# motor_driver_current_sensor.net
KiCad netlist of a schematic drawn in Altium Designer
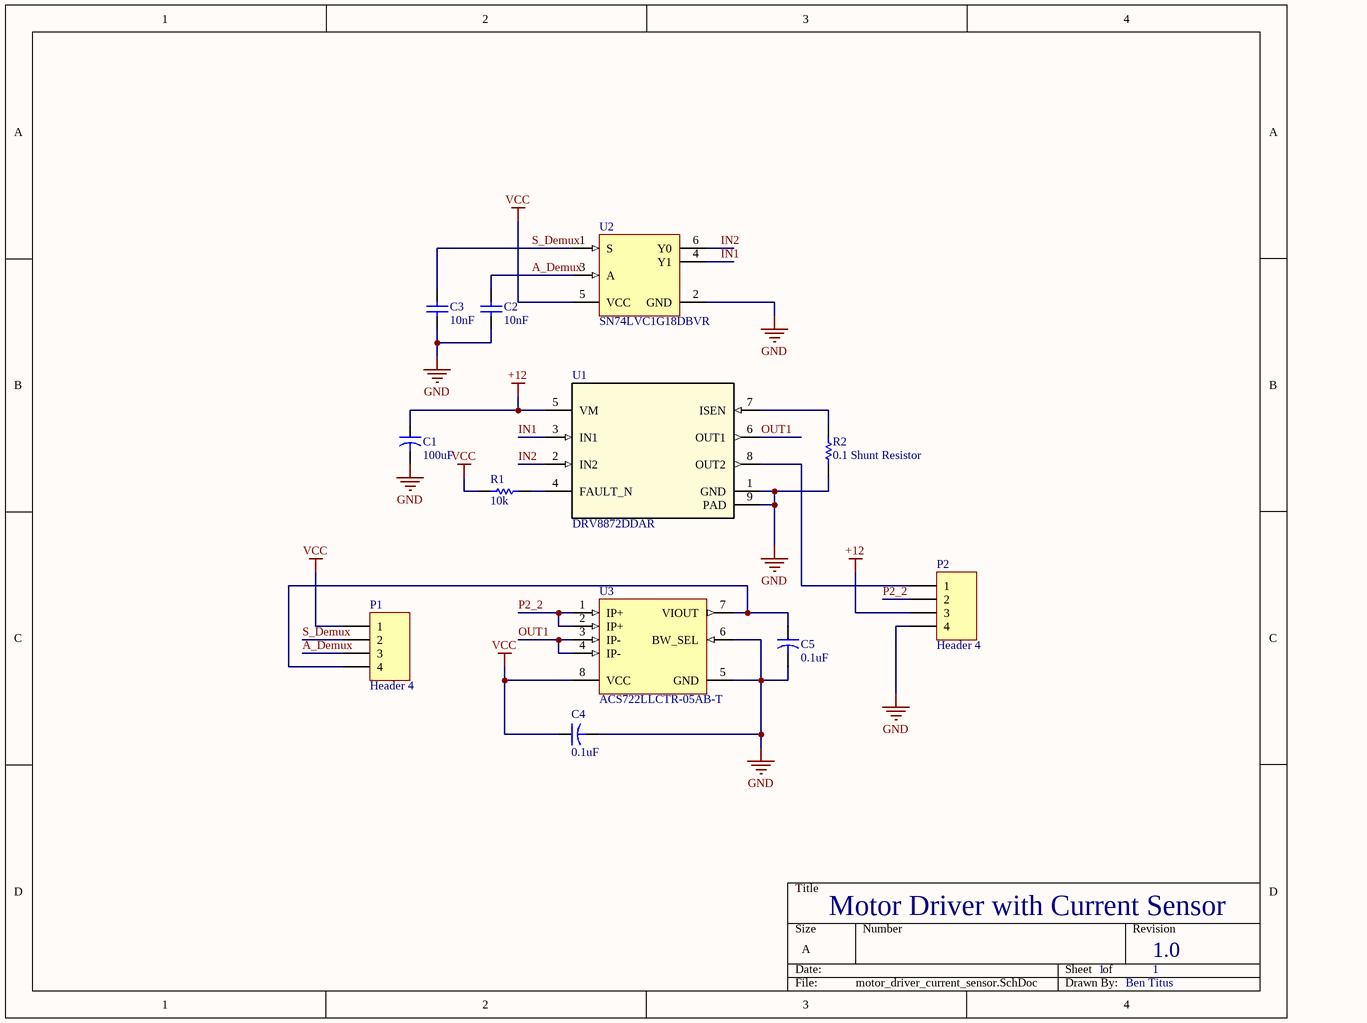
[diagram p0: motor_driver_current_sensor.SchDoc]

(export (version "E")
  (design (tool "Eeschema 10.0.6"))
  (components
    (comp (ref "C1")
      (value "100uF")
      (footprint "CAPR5-4X5")
      (description "100uF Filter Capacitor")
      (fields (field (name "PUBLISHER") "Altium Limited"))
      (libsource (lib "Miscellaneous Devices") (part "Cap2"))
    )
    (comp (ref "C2")
      (value "10nF")
      (footprint "CAPC0805(2012)145_L")
      (description "0805 (2012 Metric) Chip Capacitor")
      (libsource (lib "Altium Content Vault") (part "CAP_5"))
    )
    (comp (ref "C3")
      (value "10nF")
      (footprint "CAPC0805(2012)145_L")
      (description "0805 (2012 Metric) Chip Capacitor")
      (libsource (lib "Altium Content Vault") (part "CAP_5"))
    )
    (comp (ref "C4")
      (value "0.1uF")
      (footprint "CAPR5-4X5")
      (description "Capacitor")
      (fields (field (name "PUBLISHER") "Altium Limited"))
      (libsource (lib "Miscellaneous Devices") (part "Cap2"))
    )
    (comp (ref "C5")
      (value "0.1uF")
      (footprint "CAPR5-4X5")
      (description "Capacitor")
      (fields (field (name "PUBLISHER") "Altium Limited"))
      (libsource (lib "Miscellaneous Devices") (part "Cap2"))
    )
    (comp (ref "P1")
      (value "Header 4")
      (footprint "HDR1X4")
      (description "Header, 4-Pin")
      (fields (field (name "PUBLISHER") "Altium Limited"))
      (libsource (lib "Miscellaneous Connectors") (part "Header 4"))
    )
    (comp (ref "P2")
      (value "Header 4")
      (footprint "HDR1X4")
      (description "Header, 4-Pin")
      (fields (field (name "PUBLISHER") "Altium Limited"))
      (libsource (lib "Miscellaneous Connectors") (part "Header 4"))
    )
    (comp (ref "R1")
      (value "10k")
      (footprint "RESC0805(2012)_L")
      (description "0805 (2012 Metric) Chip Resistor")
      (libsource (lib "Altium Content Vault") (part "RES_3"))
    )
    (comp (ref "R2")
      (value "0.1 Shunt Resistor")
      (footprint "RESC2512(6432)_L")
      (description "2512 (6432 Metric) Chip Resistor")
      (libsource (lib "Altium Content Vault") (part "RES_3"))
    )
    (comp (ref "U1")
      (value "DRV8872DDAR")
      (footprint "DDA0008H_N")
      (description "Imported")
      (fields
        (field (name "ALTERNATE_PARTNUMBER") "DRV8872DDA")
        (field (name "MANUFACTURER") "Texas Instruments")
      )
      (libsource (lib "Custom_Lib") (part "DRV8872DDAR"))
    )
    (comp (ref "U2")
      (value "SN74LVC1G18DBVR")
      (footprint "DBV0006A_L")
      (description "One of Two Noninverting Demultiplexer with 3-State Deselected Output, DBV0006A, LARGE T&R")
      (fields
        (field (name "MANUFACTURER") "Texas Instruments")
        (field (name "GENERIC PART NUMBER") "SN74LVC1G18")
      )
      (libsource (lib "Altium Content Vault") (part "TI-SN74LVC1G18-6"))
    )
    (comp (ref "U3")
      (value "ACS722LLCTR-05AB-T")
      (footprint "ALEG-LC-8_V")
      (libsource (lib "Altium Content Vault") (part "ALEG-ACS722-SOIC-8"))
    )
  )
  (nets
    (net (code "1") (name "+12") (class "Default")
      (node (ref "C1") (pin "1") (pinfunction "1_1") (pintype "passive"))
      (node (ref "P2") (pin "3") (pinfunction "3_3") (pintype "passive"))
      (node (ref "U1") (pin "5") (pinfunction "VM_5") (pintype "power_in"))
    )
    (net (code "2") (name "/A_Demux") (class "Default")
      (node (ref "C2") (pin "2") (pinfunction "2_2") (pintype "passive"))
      (node (ref "P1") (pin "3") (pinfunction "3_3") (pintype "passive"))
      (node (ref "U2") (pin "3") (pinfunction "A_3") (pintype "input"))
    )
    (net (code "3") (name "/IN1") (class "Default")
      (node (ref "U1") (pin "3") (pinfunction "IN1_3") (pintype "input"))
      (node (ref "U2") (pin "4") (pinfunction "Y1_4") (pintype "tri_state"))
    )
    (net (code "4") (name "/IN2") (class "Default")
      (node (ref "U1") (pin "2") (pinfunction "IN2_2") (pintype "input"))
      (node (ref "U2") (pin "6") (pinfunction "Y0_6") (pintype "tri_state"))
    )
    (net (code "5") (name "/OUT1") (class "Default")
      (node (ref "U1") (pin "6") (pinfunction "OUT1_6") (pintype "output"))
      (node (ref "U3") (pin "3") (pinfunction "IP-_3") (pintype "input"))
      (node (ref "U3") (pin "4") (pinfunction "IP-_4") (pintype "input"))
    )
    (net (code "6") (name "/P2_2") (class "Default")
      (node (ref "P2") (pin "2") (pinfunction "2_2") (pintype "passive"))
      (node (ref "U3") (pin "1") (pinfunction "IP+_1") (pintype "input"))
      (node (ref "U3") (pin "2") (pinfunction "IP+_2") (pintype "input"))
    )
    (net (code "7") (name "/S_Demux") (class "Default")
      (node (ref "C3") (pin "2") (pinfunction "2_2") (pintype "passive"))
      (node (ref "P1") (pin "2") (pinfunction "2_2") (pintype "passive"))
      (node (ref "U2") (pin "1") (pinfunction "S_1") (pintype "input"))
    )
    (net (code "8") (name "GND") (class "Default")
      (node (ref "C1") (pin "2") (pinfunction "2_2") (pintype "passive"))
      (node (ref "C2") (pin "1") (pinfunction "1_1") (pintype "passive"))
      (node (ref "C3") (pin "1") (pinfunction "1_1") (pintype "passive"))
      (node (ref "C4") (pin "2") (pinfunction "2_2") (pintype "passive"))
      (node (ref "C5") (pin "2") (pinfunction "2_2") (pintype "passive"))
      (node (ref "P2") (pin "4") (pinfunction "4_4") (pintype "passive"))
      (node (ref "R2") (pin "1") (pinfunction "1_1") (pintype "passive"))
      (node (ref "U1") (pin "1") (pinfunction "GND_1") (pintype "power_in"))
      (node (ref "U1") (pin "9") (pinfunction "PAD_9") (pintype "power_in"))
      (node (ref "U2") (pin "2") (pinfunction "GND_2") (pintype "power_in"))
      (node (ref "U3") (pin "5") (pinfunction "GND_5") (pintype "power_in"))
      (node (ref "U3") (pin "6") (pinfunction "BW_SEL_6") (pintype "input"))
    )
    (net (code "9") (name "Net-(U1-FAULT_N)") (class "Default")
      (node (ref "R1") (pin "2") (pinfunction "2_2") (pintype "passive"))
      (node (ref "U1") (pin "4") (pinfunction "FAULT_N_4") (pintype "open_collector"))
    )
    (net (code "10") (name "Net-(U1-ISEN)") (class "Default")
      (node (ref "R2") (pin "2") (pinfunction "2_2") (pintype "passive"))
      (node (ref "U1") (pin "7") (pinfunction "ISEN_7") (pintype "input"))
    )
    (net (code "11") (name "Net-(U1-OUT2)") (class "Default")
      (node (ref "P2") (pin "1") (pinfunction "1_1") (pintype "passive"))
      (node (ref "U1") (pin "8") (pinfunction "OUT2_8") (pintype "output"))
    )
    (net (code "12") (name "Net-(U3-VIOUT)") (class "Default")
      (node (ref "C5") (pin "1") (pinfunction "1_1") (pintype "passive"))
      (node (ref "P1") (pin "4") (pinfunction "4_4") (pintype "passive"))
      (node (ref "U3") (pin "7") (pinfunction "VIOUT_7") (pintype "output"))
    )
    (net (code "13") (name "VCC") (class "Default")
      (node (ref "C4") (pin "1") (pinfunction "1_1") (pintype "passive"))
      (node (ref "P1") (pin "1") (pinfunction "1_1") (pintype "passive"))
      (node (ref "R1") (pin "1") (pinfunction "1_1") (pintype "passive"))
      (node (ref "U2") (pin "5") (pinfunction "VCC_5") (pintype "power_in"))
      (node (ref "U3") (pin "8") (pinfunction "VCC_8") (pintype "power_in"))
    )
  )
)
